# SoC_MMC.net
KiCad netlist of a schematic drawn in Altium Designer
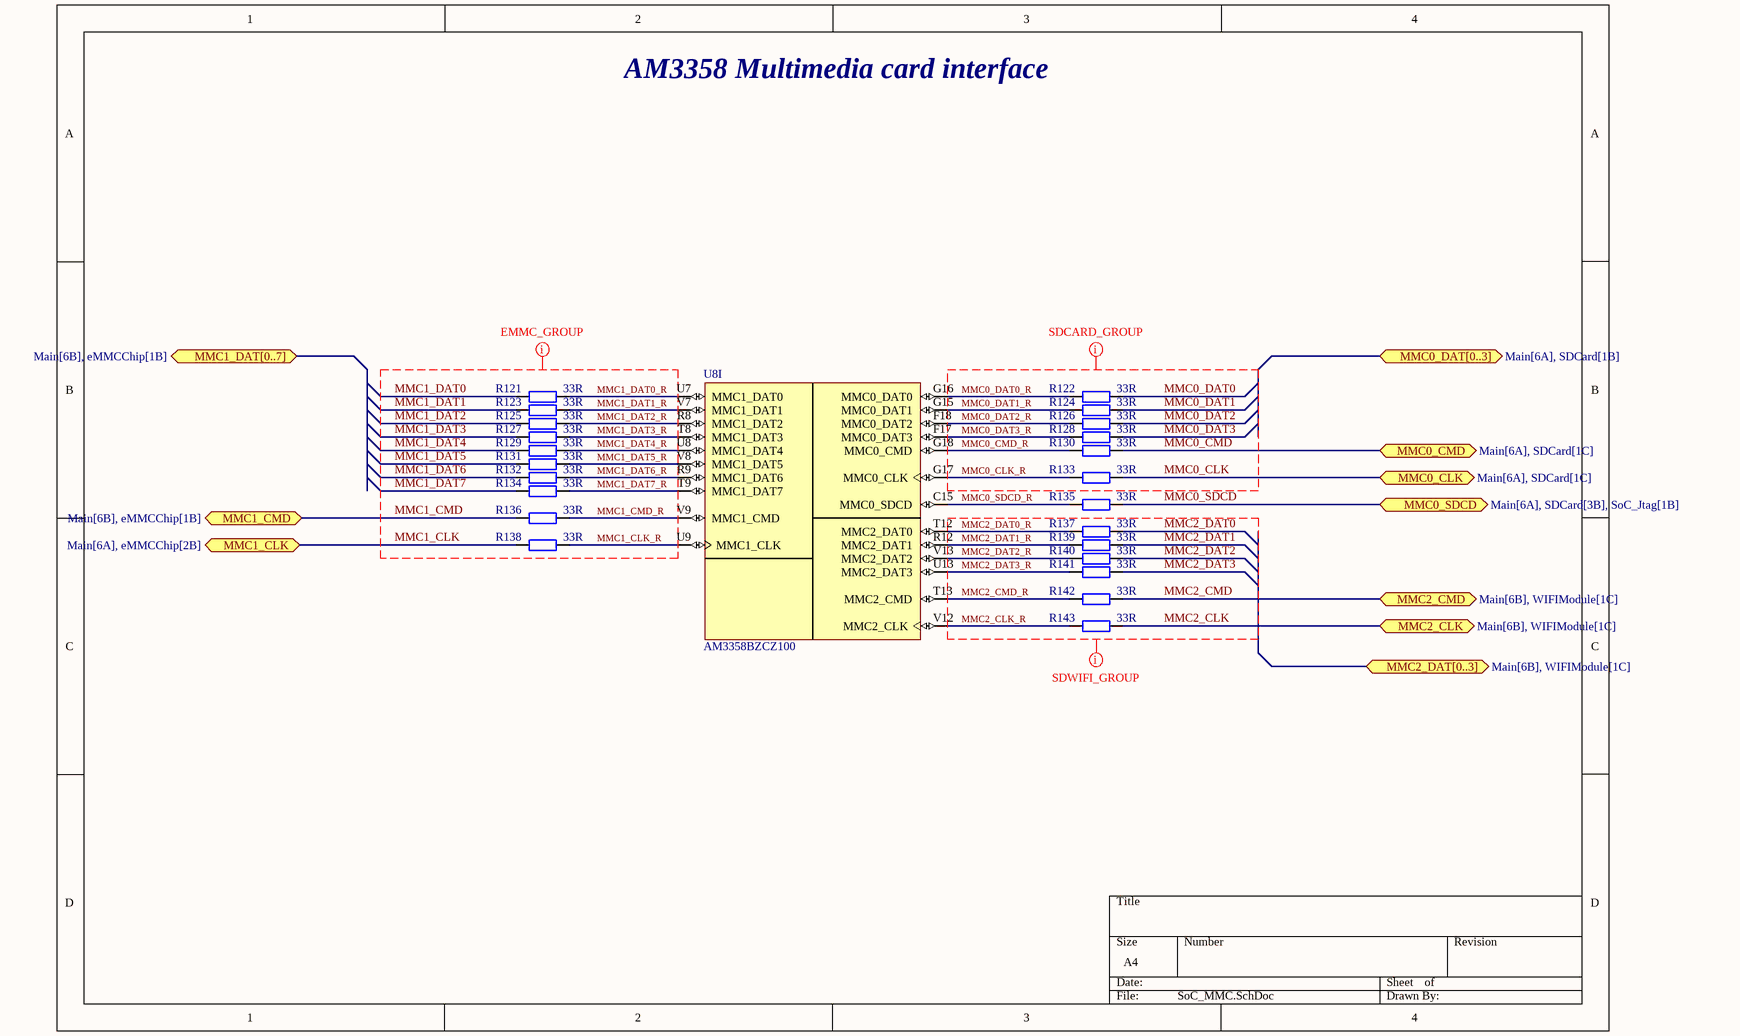
[diagram p0: SoC_MMC.SchDoc]

(export (version "E")
  (design (tool "Eeschema 10.0.6"))
  (components
    (comp (ref "R121")
      (value "33R")
      (footprint "R_0402")
      (description "Resistor 0402 SMD")
      (libsource (lib "tor1kkLib") (part "R_0402"))
    )
    (comp (ref "R122")
      (value "33R")
      (footprint "R_0402")
      (description "Resistor 0402 SMD")
      (libsource (lib "tor1kkLib") (part "R_0402"))
    )
    (comp (ref "R123")
      (value "33R")
      (footprint "R_0402")
      (description "Resistor 0402 SMD")
      (libsource (lib "tor1kkLib") (part "R_0402"))
    )
    (comp (ref "R124")
      (value "33R")
      (footprint "R_0402")
      (description "Resistor 0402 SMD")
      (libsource (lib "tor1kkLib") (part "R_0402"))
    )
    (comp (ref "R125")
      (value "33R")
      (footprint "R_0402")
      (description "Resistor 0402 SMD")
      (libsource (lib "tor1kkLib") (part "R_0402"))
    )
    (comp (ref "R126")
      (value "33R")
      (footprint "R_0402")
      (description "Resistor 0402 SMD")
      (libsource (lib "tor1kkLib") (part "R_0402"))
    )
    (comp (ref "R127")
      (value "33R")
      (footprint "R_0402")
      (description "Resistor 0402 SMD")
      (libsource (lib "tor1kkLib") (part "R_0402"))
    )
    (comp (ref "R128")
      (value "33R")
      (footprint "R_0402")
      (description "Resistor 0402 SMD")
      (libsource (lib "tor1kkLib") (part "R_0402"))
    )
    (comp (ref "R129")
      (value "33R")
      (footprint "R_0402")
      (description "Resistor 0402 SMD")
      (libsource (lib "tor1kkLib") (part "R_0402"))
    )
    (comp (ref "R130")
      (value "33R")
      (footprint "R_0402")
      (description "Resistor 0402 SMD")
      (libsource (lib "tor1kkLib") (part "R_0402"))
    )
    (comp (ref "R131")
      (value "33R")
      (footprint "R_0402")
      (description "Resistor 0402 SMD")
      (libsource (lib "tor1kkLib") (part "R_0402"))
    )
    (comp (ref "R132")
      (value "33R")
      (footprint "R_0402")
      (description "Resistor 0402 SMD")
      (libsource (lib "tor1kkLib") (part "R_0402"))
    )
    (comp (ref "R133")
      (value "33R")
      (footprint "R_0402")
      (description "Resistor 0402 SMD")
      (libsource (lib "tor1kkLib") (part "R_0402"))
    )
    (comp (ref "R134")
      (value "33R")
      (footprint "R_0402")
      (description "Resistor 0402 SMD")
      (libsource (lib "tor1kkLib") (part "R_0402"))
    )
    (comp (ref "R135")
      (value "33R")
      (footprint "R_0402")
      (description "Resistor 0402 SMD")
      (libsource (lib "tor1kkLib") (part "R_0402"))
    )
    (comp (ref "R136")
      (value "33R")
      (footprint "R_0402")
      (description "Resistor 0402 SMD")
      (libsource (lib "tor1kkLib") (part "R_0402"))
    )
    (comp (ref "R137")
      (value "33R")
      (footprint "R_0402")
      (description "Resistor 0402 SMD")
      (libsource (lib "tor1kkLib") (part "R_0402"))
    )
    (comp (ref "R138")
      (value "33R")
      (footprint "R_0402")
      (description "Resistor 0402 SMD")
      (libsource (lib "tor1kkLib") (part "R_0402"))
    )
    (comp (ref "R139")
      (value "33R")
      (footprint "R_0402")
      (description "Resistor 0402 SMD")
      (libsource (lib "tor1kkLib") (part "R_0402"))
    )
    (comp (ref "R140")
      (value "33R")
      (footprint "R_0402")
      (description "Resistor 0402 SMD")
      (libsource (lib "tor1kkLib") (part "R_0402"))
    )
    (comp (ref "R141")
      (value "33R")
      (footprint "R_0402")
      (description "Resistor 0402 SMD")
      (libsource (lib "tor1kkLib") (part "R_0402"))
    )
    (comp (ref "R142")
      (value "33R")
      (footprint "R_0402")
      (description "Resistor 0402 SMD")
      (libsource (lib "tor1kkLib") (part "R_0402"))
    )
    (comp (ref "R143")
      (value "33R")
      (footprint "R_0402")
      (description "Resistor 0402 SMD")
      (libsource (lib "tor1kkLib") (part "R_0402"))
    )
    (comp (ref "U8")
      (value "AM3358BZCZ100")
      (footprint "BGA324C80P18X18_1500X1500X140")
      (description "ARM-ASeries 1GHz NFBGA-324 Microcontrollers (MCU/MPU/SOC) ROHS")
      (fields (field (name "MANUFACTURER") "Texas Instruments"))
      (libsource (lib "tor1kkLib") (part "AM3358BZCZ100"))
    )
  )
  (nets
    (net (code "1") (name "/MMC0_CLK") (class "Default") (node (ref "R133") (pin "2") (pintype "passive")))
    (net (code "2") (name "/MMC0_CLK_R") (class "Default")
      (node (ref "R133") (pin "1") (pintype "passive"))
      (node (ref "U8") (pin "G17") (pinfunction "MMC0_CLK_G17") (pintype "bidirectional"))
    )
    (net (code "3") (name "/MMC0_CMD") (class "Default") (node (ref "R130") (pin "2") (pintype "passive")))
    (net (code "4") (name "/MMC0_CMD_R") (class "Default")
      (node (ref "R130") (pin "1") (pintype "passive"))
      (node (ref "U8") (pin "G18") (pinfunction "MMC0_CMD_G18") (pintype "bidirectional"))
    )
    (net (code "5") (name "/MMC0_DAT0") (class "Default") (node (ref "R122") (pin "2") (pintype "passive")))
    (net (code "6") (name "/MMC0_DAT0_R") (class "Default")
      (node (ref "R122") (pin "1") (pintype "passive"))
      (node (ref "U8") (pin "G16") (pinfunction "MMC0_DAT0_G16") (pintype "bidirectional"))
    )
    (net (code "7") (name "/MMC0_DAT1") (class "Default") (node (ref "R124") (pin "2") (pintype "passive")))
    (net (code "8") (name "/MMC0_DAT1_R") (class "Default")
      (node (ref "R124") (pin "1") (pintype "passive"))
      (node (ref "U8") (pin "G15") (pinfunction "MMC0_DAT1_G15") (pintype "bidirectional"))
    )
    (net (code "9") (name "/MMC0_DAT2") (class "Default") (node (ref "R126") (pin "2") (pintype "passive")))
    (net (code "10") (name "/MMC0_DAT2_R") (class "Default")
      (node (ref "R126") (pin "1") (pintype "passive"))
      (node (ref "U8") (pin "F18") (pinfunction "MMC0_DAT2_F18") (pintype "bidirectional"))
    )
    (net (code "11") (name "/MMC0_DAT3") (class "Default") (node (ref "R128") (pin "2") (pintype "passive")))
    (net (code "12") (name "/MMC0_DAT3_R") (class "Default")
      (node (ref "R128") (pin "1") (pintype "passive"))
      (node (ref "U8") (pin "F17") (pinfunction "MMC0_DAT3_F17") (pintype "bidirectional"))
    )
    (net (code "14") (name "/MMC0_SDCD") (class "Default") (node (ref "R135") (pin "2") (pintype "passive")))
    (net (code "15") (name "/MMC0_SDCD_R") (class "Default")
      (node (ref "R135") (pin "1") (pintype "passive"))
      (node (ref "U8") (pin "C15") (pinfunction "MMC0_SDCD_C15") (pintype "bidirectional"))
    )
    (net (code "16") (name "/MMC1_CLK") (class "Default") (node (ref "R138") (pin "1") (pintype "passive")))
    (net (code "17") (name "/MMC1_CLK_R") (class "Default")
      (node (ref "R138") (pin "2") (pintype "passive"))
      (node (ref "U8") (pin "U9") (pinfunction "MMC1_CLK_U9") (pintype "bidirectional"))
    )
    (net (code "18") (name "/MMC1_CMD") (class "Default") (node (ref "R136") (pin "1") (pintype "passive")))
    (net (code "19") (name "/MMC1_CMD_R") (class "Default")
      (node (ref "R136") (pin "2") (pintype "passive"))
      (node (ref "U8") (pin "V9") (pinfunction "MMC1_CMD_V9") (pintype "bidirectional"))
    )
    (net (code "20") (name "/MMC1_DAT0") (class "Default") (node (ref "R121") (pin "1") (pintype "passive")))
    (net (code "21") (name "/MMC1_DAT0_R") (class "Default")
      (node (ref "R121") (pin "2") (pintype "passive"))
      (node (ref "U8") (pin "U7") (pinfunction "MMC1_DAT0_U7") (pintype "bidirectional"))
    )
    (net (code "22") (name "/MMC1_DAT1") (class "Default") (node (ref "R123") (pin "1") (pintype "passive")))
    (net (code "23") (name "/MMC1_DAT1_R") (class "Default")
      (node (ref "R123") (pin "2") (pintype "passive"))
      (node (ref "U8") (pin "V7") (pinfunction "MMC1_DAT1_V7") (pintype "bidirectional"))
    )
    (net (code "24") (name "/MMC1_DAT2") (class "Default") (node (ref "R125") (pin "1") (pintype "passive")))
    (net (code "25") (name "/MMC1_DAT2_R") (class "Default")
      (node (ref "R125") (pin "2") (pintype "passive"))
      (node (ref "U8") (pin "R8") (pinfunction "MMC1_DAT2_R8") (pintype "bidirectional"))
    )
    (net (code "26") (name "/MMC1_DAT3") (class "Default") (node (ref "R127") (pin "1") (pintype "passive")))
    (net (code "27") (name "/MMC1_DAT3_R") (class "Default")
      (node (ref "R127") (pin "2") (pintype "passive"))
      (node (ref "U8") (pin "T8") (pinfunction "MMC1_DAT3_T8") (pintype "bidirectional"))
    )
    (net (code "28") (name "/MMC1_DAT4") (class "Default") (node (ref "R129") (pin "1") (pintype "passive")))
    (net (code "29") (name "/MMC1_DAT4_R") (class "Default")
      (node (ref "R129") (pin "2") (pintype "passive"))
      (node (ref "U8") (pin "U8") (pinfunction "MMC1_DAT4_U8") (pintype "bidirectional"))
    )
    (net (code "30") (name "/MMC1_DAT5") (class "Default") (node (ref "R131") (pin "1") (pintype "passive")))
    (net (code "31") (name "/MMC1_DAT5_R") (class "Default")
      (node (ref "R131") (pin "2") (pintype "passive"))
      (node (ref "U8") (pin "V8") (pinfunction "MMC1_DAT5_V8") (pintype "bidirectional"))
    )
    (net (code "32") (name "/MMC1_DAT6") (class "Default") (node (ref "R132") (pin "1") (pintype "passive")))
    (net (code "33") (name "/MMC1_DAT6_R") (class "Default")
      (node (ref "R132") (pin "2") (pintype "passive"))
      (node (ref "U8") (pin "R9") (pinfunction "MMC1_DAT6_R9") (pintype "bidirectional"))
    )
    (net (code "34") (name "/MMC1_DAT7") (class "Default") (node (ref "R134") (pin "1") (pintype "passive")))
    (net (code "35") (name "/MMC1_DAT7_R") (class "Default")
      (node (ref "R134") (pin "2") (pintype "passive"))
      (node (ref "U8") (pin "T9") (pinfunction "MMC1_DAT7_T9") (pintype "bidirectional"))
    )
    (net (code "37") (name "/MMC2_CLK") (class "Default") (node (ref "R143") (pin "2") (pintype "passive")))
    (net (code "38") (name "/MMC2_CLK_R") (class "Default")
      (node (ref "R143") (pin "1") (pintype "passive"))
      (node (ref "U8") (pin "V12") (pinfunction "MMC2_CLK_V12") (pintype "bidirectional"))
    )
    (net (code "39") (name "/MMC2_CMD") (class "Default") (node (ref "R142") (pin "2") (pintype "passive")))
    (net (code "40") (name "/MMC2_CMD_R") (class "Default")
      (node (ref "R142") (pin "1") (pintype "passive"))
      (node (ref "U8") (pin "T13") (pinfunction "MMC2_CMD_T13") (pintype "bidirectional"))
    )
    (net (code "41") (name "/MMC2_DAT0") (class "Default") (node (ref "R137") (pin "2") (pintype "passive")))
    (net (code "42") (name "/MMC2_DAT0_R") (class "Default")
      (node (ref "R137") (pin "1") (pintype "passive"))
      (node (ref "U8") (pin "T12") (pinfunction "MMC2_DAT0_T12") (pintype "bidirectional"))
    )
    (net (code "43") (name "/MMC2_DAT1") (class "Default") (node (ref "R139") (pin "2") (pintype "passive")))
    (net (code "44") (name "/MMC2_DAT1_R") (class "Default")
      (node (ref "R139") (pin "1") (pintype "passive"))
      (node (ref "U8") (pin "R12") (pinfunction "MMC2_DAT1_R12") (pintype "bidirectional"))
    )
    (net (code "45") (name "/MMC2_DAT2") (class "Default") (node (ref "R140") (pin "2") (pintype "passive")))
    (net (code "46") (name "/MMC2_DAT2_R") (class "Default")
      (node (ref "R140") (pin "1") (pintype "passive"))
      (node (ref "U8") (pin "V13") (pinfunction "MMC2_DAT2_V13") (pintype "bidirectional"))
    )
    (net (code "47") (name "/MMC2_DAT3") (class "Default") (node (ref "R141") (pin "2") (pintype "passive")))
    (net (code "48") (name "/MMC2_DAT3_R") (class "Default")
      (node (ref "R141") (pin "1") (pintype "passive"))
      (node (ref "U8") (pin "U13") (pinfunction "MMC2_DAT3_U13") (pintype "bidirectional"))
    )
  )
)
